# MOSFET.net
KiCad netlist of a schematic drawn in EAGLE
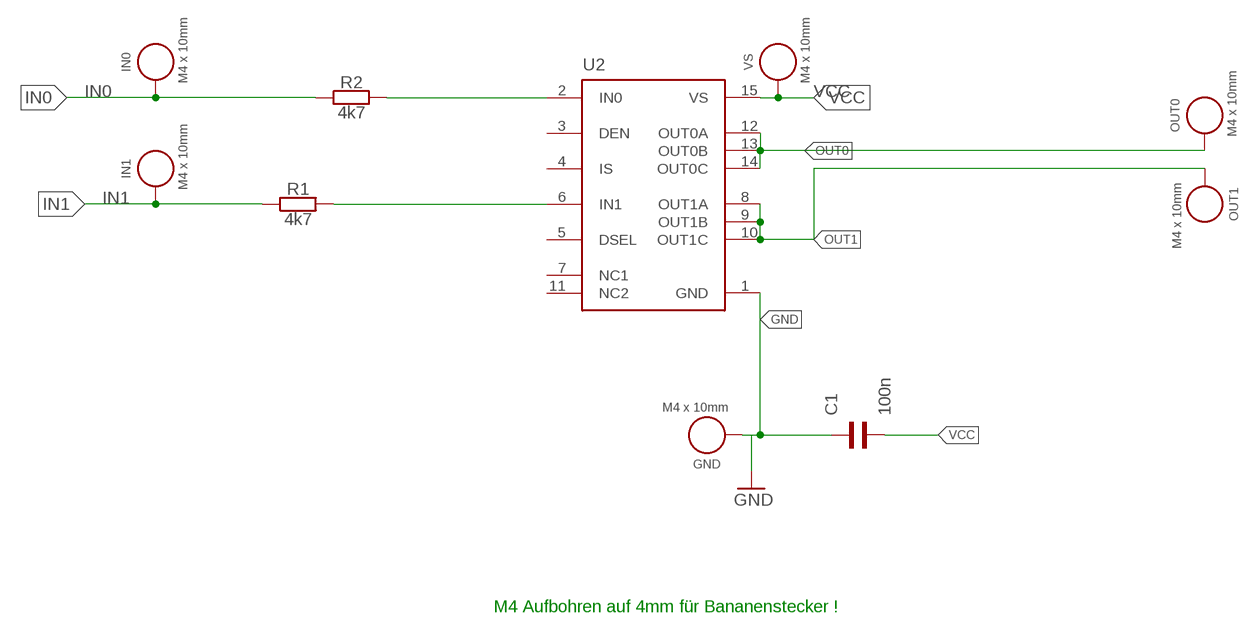
[diagram p0: schematic, sheet 1]

(export (version "E")
  (design (tool "Eeschema 10.0.6"))
  (components
    (comp (ref "C1")
      (value "100n")
      (footprint "eagle-import:WCAP-CSGP_0402")
      (libsource (lib "eagle-import") (part "WCAP-CSGP_0402_885012205037"))
    )
    (comp (ref "GND")
      (value "M4 x 10mm")
      (footprint "eagle-import:WA-SMSI_9774100482")
      (libsource (lib "eagle-import") (part "WA-SMSI_9774XXX482_9774100482"))
    )
    (comp (ref "IN0")
      (value "M4 x 10mm")
      (footprint "eagle-import:WA-SMSI_9774100482")
      (libsource (lib "eagle-import") (part "WA-SMSI_9774XXX482_9774100482"))
    )
    (comp (ref "IN1")
      (value "M4 x 10mm")
      (footprint "eagle-import:WA-SMSI_9774100482")
      (libsource (lib "eagle-import") (part "WA-SMSI_9774XXX482_9774100482"))
    )
    (comp (ref "OUT0")
      (value "M4 x 10mm")
      (footprint "eagle-import:WA-SMSI_9774100482")
      (libsource (lib "eagle-import") (part "WA-SMSI_9774XXX482_9774100482"))
    )
    (comp (ref "OUT1")
      (value "M4 x 10mm")
      (footprint "eagle-import:WA-SMSI_9774100482")
      (libsource (lib "eagle-import") (part "WA-SMSI_9774XXX482_9774100482"))
    )
    (comp (ref "R1")
      (value "4k7")
      (footprint "eagle-import:WCAP-CSRF_0402")
      (libsource (lib "eagle-import") (part "R-EU_WCAP-CSGP_0402"))
    )
    (comp (ref "R2")
      (value "4k7")
      (footprint "eagle-import:WCAP-CSRF_0402")
      (libsource (lib "eagle-import") (part "R-EU_WCAP-CSGP_0402"))
    )
    (comp (ref "U2")
      (value "BTS7030-2EPA")
      (footprint "eagle-import:SOP65P600X115-15N-V")
      (libsource (lib "eagle-import") (part "BTS7030-2EPA"))
    )
    (comp (ref "VS")
      (value "M4 x 10mm")
      (footprint "eagle-import:WA-SMSI_9774100482")
      (libsource (lib "eagle-import") (part "WA-SMSI_9774XXX482_9774100482"))
    )
  )
  (nets
    (net (code "1") (name "GND") (class "Default")
      (node (ref "C1") (pin "2") (pinfunction "2_2") (pintype "passive"))
      (node (ref "GND") (pin "1") (pinfunction "1_1") (pintype "passive"))
      (node (ref "U2") (pin "1") (pinfunction "GND_1") (pintype "power_in"))
    )
    (net (code "2") (name "IN0") (class "Default")
      (node (ref "IN0") (pin "1") (pinfunction "1_1") (pintype "passive"))
      (node (ref "R2") (pin "1") (pinfunction "1_1") (pintype "passive"))
    )
    (net (code "3") (name "IN1") (class "Default")
      (node (ref "IN1") (pin "1") (pinfunction "1_1") (pintype "passive"))
      (node (ref "R1") (pin "1") (pinfunction "1_1") (pintype "passive"))
    )
    (net (code "4") (name "Net-(U2-IN0)") (class "Default")
      (node (ref "R2") (pin "2") (pinfunction "2_2") (pintype "passive"))
      (node (ref "U2") (pin "2") (pinfunction "IN0_2") (pintype "input"))
    )
    (net (code "5") (name "Net-(U2-IN1)") (class "Default")
      (node (ref "R1") (pin "2") (pinfunction "2_2") (pintype "passive"))
      (node (ref "U2") (pin "6") (pinfunction "IN1_6") (pintype "input"))
    )
    (net (code "6") (name "OUT0") (class "Default")
      (node (ref "OUT0") (pin "1") (pinfunction "1_1") (pintype "passive"))
      (node (ref "U2") (pin "12") (pinfunction "OUT0A_12") (pintype "output"))
      (node (ref "U2") (pin "13") (pinfunction "OUT0B_13") (pintype "output"))
      (node (ref "U2") (pin "14") (pinfunction "OUT0C_14") (pintype "output"))
    )
    (net (code "7") (name "OUT1") (class "Default")
      (node (ref "OUT1") (pin "1") (pinfunction "1_1") (pintype "passive"))
      (node (ref "U2") (pin "10") (pinfunction "OUT1C_10") (pintype "output"))
      (node (ref "U2") (pin "8") (pinfunction "OUT1A_8") (pintype "output"))
      (node (ref "U2") (pin "9") (pinfunction "OUT1B_9") (pintype "output"))
    )
    (net (code "8") (name "VCC") (class "Default")
      (node (ref "C1") (pin "1") (pinfunction "1_1") (pintype "passive"))
      (node (ref "U2") (pin "15") (pinfunction "VS_15") (pintype "power_in"))
      (node (ref "VS") (pin "1") (pinfunction "1_1") (pintype "passive"))
    )
    (net (code "9") (name "unconnected-(U2-DEN-Pad3)") (class "Default")
      (node (ref "U2") (pin "3") (pinfunction "DEN_3") (pintype "input"))
    )
    (net (code "10") (name "unconnected-(U2-DSEL-Pad5)") (class "Default")
      (node (ref "U2") (pin "5") (pinfunction "DSEL_5") (pintype "input"))
    )
    (net (code "11") (name "unconnected-(U2-IS-Pad4)") (class "Default")
      (node (ref "U2") (pin "4") (pinfunction "IS_4") (pintype "output"))
    )
    (net (code "12") (name "unconnected-(U2-NC1-Pad7)") (class "Default")
      (node (ref "U2") (pin "7") (pinfunction "NC1_7") (pintype "passive"))
    )
    (net (code "13") (name "unconnected-(U2-NC2-Pad11)") (class "Default")
      (node (ref "U2") (pin "11") (pinfunction "NC2_11") (pintype "passive"))
    )
  )
)
